# MC-test.net
KiCad netlist of a schematic drawn in EAGLE
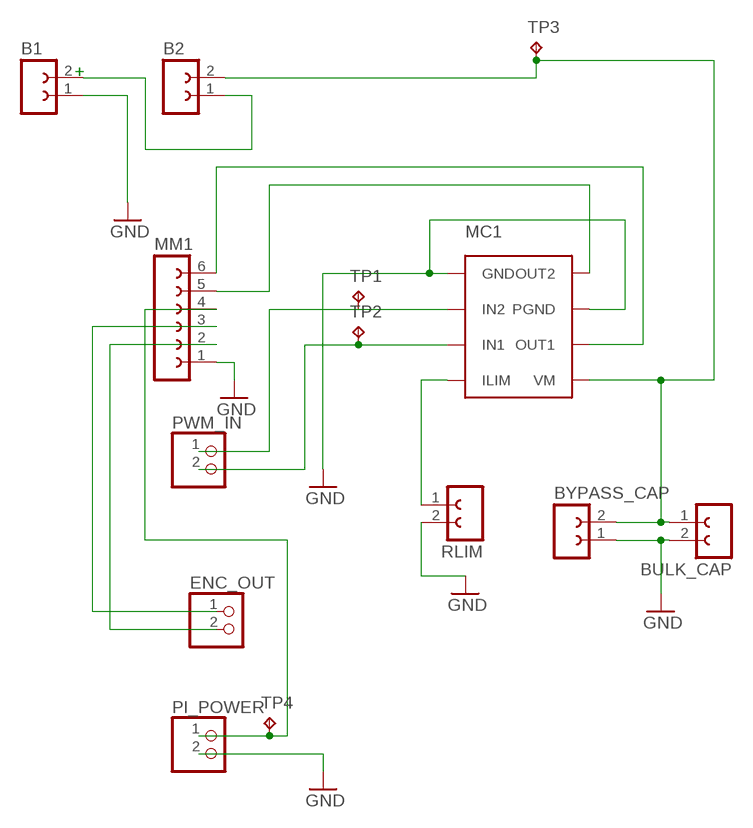
[diagram p0: schematic, sheet 1]

(export (version "E")
  (design (tool "Eeschema 10.0.6"))
  (components
    (comp (ref "B1")
      (value "FH_02X01")
      (footprint "eagle-import:FH_02X01")
      (libsource (lib "eagle-import") (part "FH_02X01"))
    )
    (comp (ref "B2")
      (value "FH_02X01")
      (footprint "eagle-import:FH_02X01")
      (libsource (lib "eagle-import") (part "FH_02X01"))
    )
    (comp (ref "BULK_CAP")
      (value "FH_02X01")
      (footprint "eagle-import:FH_02X01")
      (libsource (lib "eagle-import") (part "FH_02X01"))
    )
    (comp (ref "BYPASS_CAP")
      (value "FH_02X01")
      (footprint "eagle-import:FH_02X01")
      (libsource (lib "eagle-import") (part "FH_02X01"))
    )
    (comp (ref "ENC_OUT")
      (value "PINHD-1X2")
      (footprint "eagle-import:1X02")
      (libsource (lib "eagle-import") (part "PINHD-1X2"))
    )
    (comp (ref "MC1")
      (value "DRV8871")
      (footprint "eagle-import:SO-8_POWERPAD")
      (libsource (lib "eagle-import") (part "DRV8871"))
    )
    (comp (ref "MM1")
      (value "FE06-1")
      (footprint "eagle-import:FE06")
      (libsource (lib "eagle-import") (part "FE06-1"))
    )
    (comp (ref "PI_POWER")
      (value "PINHD-1X2")
      (footprint "eagle-import:1X02")
      (libsource (lib "eagle-import") (part "PINHD-1X2"))
    )
    (comp (ref "PWM_IN")
      (value "PINHD-1X2")
      (footprint "eagle-import:1X02")
      (libsource (lib "eagle-import") (part "PINHD-1X2"))
    )
    (comp (ref "RLIM")
      (value "FH_02X01")
      (footprint "eagle-import:FH_02X01")
      (fields (field (name "SPICEPREFIX") "B"))
      (libsource (lib "eagle-import") (part "FH_02X01"))
    )
    (comp (ref "TP1")
      (value "TPTP15SQ")
      (footprint "eagle-import:TP15SQ")
      (libsource (lib "eagle-import") (part "TPTP15SQ"))
    )
    (comp (ref "TP2")
      (value "TPTP15SQ")
      (footprint "eagle-import:TP15SQ")
      (libsource (lib "eagle-import") (part "TPTP15SQ"))
    )
    (comp (ref "TP3")
      (value "TPTP15SQ")
      (footprint "eagle-import:TP15SQ")
      (libsource (lib "eagle-import") (part "TPTP15SQ"))
    )
    (comp (ref "TP4")
      (value "TPTP15SQ")
      (footprint "eagle-import:TP15SQ")
      (libsource (lib "eagle-import") (part "TPTP15SQ"))
    )
  )
  (nets
    (net (code "1") (name "GND") (class "Default")
      (node (ref "B1") (pin "1") (pinfunction "1_1") (pintype "passive"))
      (node (ref "BULK_CAP") (pin "2") (pinfunction "2_2") (pintype "passive"))
      (node (ref "BYPASS_CAP") (pin "1") (pinfunction "1_1") (pintype "passive"))
      (node (ref "MC1") (pin "1") (pinfunction "GND_1") (pintype "power_in"))
      (node (ref "MC1") (pin "7") (pinfunction "PGND_7") (pintype "power_in"))
      (node (ref "MM1") (pin "1") (pinfunction "1_1") (pintype "passive"))
      (node (ref "PI_POWER") (pin "2") (pinfunction "2_2") (pintype "passive"))
      (node (ref "RLIM") (pin "2") (pinfunction "2_2") (pintype "passive"))
    )
    (net (code "2") (name "Net-(B1-Pad2)") (class "Default")
      (node (ref "B1") (pin "2") (pinfunction "2_2") (pintype "passive"))
      (node (ref "B2") (pin "1") (pinfunction "1_1") (pintype "passive"))
    )
    (net (code "3") (name "Net-(ENC_OUT-Pad1)") (class "Default")
      (node (ref "ENC_OUT") (pin "1") (pinfunction "1_1") (pintype "passive"))
      (node (ref "MM1") (pin "3") (pinfunction "3_3") (pintype "passive"))
    )
    (net (code "4") (name "Net-(ENC_OUT-Pad2)") (class "Default")
      (node (ref "ENC_OUT") (pin "2") (pinfunction "2_2") (pintype "passive"))
      (node (ref "MM1") (pin "2") (pinfunction "2_2") (pintype "passive"))
    )
    (net (code "5") (name "Net-(MC1-ILIM)") (class "Default")
      (node (ref "MC1") (pin "4") (pinfunction "ILIM_4") (pintype "input"))
      (node (ref "RLIM") (pin "1") (pinfunction "1_1") (pintype "passive"))
    )
    (net (code "6") (name "Net-(MC1-IN1)") (class "Default")
      (node (ref "MC1") (pin "3") (pinfunction "IN1_3") (pintype "input"))
      (node (ref "PWM_IN") (pin "2") (pinfunction "2_2") (pintype "passive"))
      (node (ref "TP2") (pin "TP") (pinfunction "TP_TP") (pintype "input"))
    )
    (net (code "7") (name "Net-(MC1-IN2)") (class "Default")
      (node (ref "MC1") (pin "2") (pinfunction "IN2_2") (pintype "input"))
      (node (ref "PWM_IN") (pin "1") (pinfunction "1_1") (pintype "passive"))
      (node (ref "TP1") (pin "TP") (pinfunction "TP_TP") (pintype "input"))
    )
    (net (code "8") (name "Net-(MC1-OUT1)") (class "Default")
      (node (ref "MC1") (pin "6") (pinfunction "OUT1_6") (pintype "output"))
      (node (ref "MM1") (pin "6") (pinfunction "6_6") (pintype "passive"))
    )
    (net (code "9") (name "Net-(MC1-OUT2)") (class "Default")
      (node (ref "MC1") (pin "8") (pinfunction "OUT2_8") (pintype "output"))
      (node (ref "MM1") (pin "5") (pinfunction "5_5") (pintype "passive"))
    )
    (net (code "10") (name "Net-(MC1-VM)") (class "Default")
      (node (ref "B2") (pin "2") (pinfunction "2_2") (pintype "passive"))
      (node (ref "BULK_CAP") (pin "1") (pinfunction "1_1") (pintype "passive"))
      (node (ref "BYPASS_CAP") (pin "2") (pinfunction "2_2") (pintype "passive"))
      (node (ref "MC1") (pin "5") (pinfunction "VM_5") (pintype "power_in"))
      (node (ref "TP3") (pin "TP") (pinfunction "TP_TP") (pintype "input"))
    )
    (net (code "11") (name "Net-(MM1-Pad4)") (class "Default")
      (node (ref "MM1") (pin "4") (pinfunction "4_4") (pintype "passive"))
      (node (ref "PI_POWER") (pin "1") (pinfunction "1_1") (pintype "passive"))
      (node (ref "TP4") (pin "TP") (pinfunction "TP_TP") (pintype "input"))
    )
  )
)
